# board.net
KiCad netlist of a schematic drawn in EAGLE
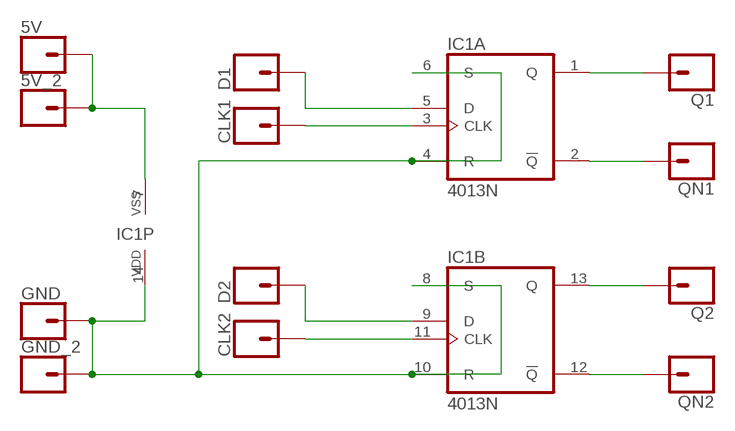
[diagram p0: schematic, sheet 1]

(export (version "E")
  (design (tool "Eeschema 10.0.6"))
  (components
    (comp (ref "5V")
      (value "CONN_01")
      (footprint "eagle-import:1X01")
      (libsource (lib "eagle-import") (part "CONN_01"))
    )
    (comp (ref "5V_2")
      (value "CONN_01")
      (footprint "eagle-import:1X01")
      (libsource (lib "eagle-import") (part "CONN_01"))
    )
    (comp (ref "CLK1")
      (value "CONN_01")
      (footprint "eagle-import:1X01")
      (libsource (lib "eagle-import") (part "CONN_01"))
    )
    (comp (ref "CLK2")
      (value "CONN_01")
      (footprint "eagle-import:1X01")
      (libsource (lib "eagle-import") (part "CONN_01"))
    )
    (comp (ref "D1")
      (value "CONN_01")
      (footprint "eagle-import:1X01")
      (libsource (lib "eagle-import") (part "CONN_01"))
    )
    (comp (ref "D2")
      (value "CONN_01")
      (footprint "eagle-import:1X01")
      (libsource (lib "eagle-import") (part "CONN_01"))
    )
    (comp (ref "GND")
      (value "CONN_01")
      (footprint "eagle-import:1X01")
      (libsource (lib "eagle-import") (part "CONN_01"))
    )
    (comp (ref "GND_2")
      (value "CONN_01")
      (footprint "eagle-import:1X01")
      (libsource (lib "eagle-import") (part "CONN_01"))
    )
    (comp (ref "IC1")
      (value "4013N")
      (footprint "eagle-import:DIL14")
      (libsource (lib "eagle-import") (part "4013N"))
    )
    (comp (ref "Q1")
      (value "CONN_01")
      (footprint "eagle-import:1X01")
      (libsource (lib "eagle-import") (part "CONN_01"))
    )
    (comp (ref "Q2")
      (value "CONN_01")
      (footprint "eagle-import:1X01")
      (libsource (lib "eagle-import") (part "CONN_01"))
    )
    (comp (ref "QN1")
      (value "CONN_01")
      (footprint "eagle-import:1X01")
      (libsource (lib "eagle-import") (part "CONN_01"))
    )
    (comp (ref "QN2")
      (value "CONN_01")
      (footprint "eagle-import:1X01")
      (libsource (lib "eagle-import") (part "CONN_01"))
    )
  )
  (nets
    (net (code "1") (name "Net-(IC1A-CLK)") (class "Default")
      (node (ref "CLK1") (pin "1") (pinfunction "1_1") (pintype "passive"))
      (node (ref "IC1") (pin "3") (pinfunction "CLK_3") (pintype "input"))
    )
    (net (code "2") (name "Net-(IC1A-D)") (class "Default")
      (node (ref "D1") (pin "1") (pinfunction "1_1") (pintype "passive"))
      (node (ref "IC1") (pin "5") (pinfunction "D_5") (pintype "input"))
    )
    (net (code "3") (name "Net-(IC1A-Q)") (class "Default")
      (node (ref "IC1") (pin "1") (pinfunction "Q_1") (pintype "output"))
      (node (ref "Q1") (pin "1") (pinfunction "1_1") (pintype "passive"))
    )
    (net (code "4") (name "Net-(IC1A-R)") (class "Default")
      (node (ref "GND") (pin "1") (pinfunction "1_1") (pintype "passive"))
      (node (ref "GND_2") (pin "1") (pinfunction "1_1") (pintype "passive"))
      (node (ref "IC1") (pin "10") (pinfunction "R_10") (pintype "input"))
      (node (ref "IC1") (pin "14") (pinfunction "VDD_14") (pintype "power_in"))
      (node (ref "IC1") (pin "4") (pinfunction "R_4") (pintype "input"))
      (node (ref "IC1") (pin "6") (pinfunction "S_6") (pintype "input"))
      (node (ref "IC1") (pin "8") (pinfunction "S_8") (pintype "input"))
    )
    (net (code "5") (name "Net-(IC1A-~{Q})") (class "Default")
      (node (ref "IC1") (pin "2") (pinfunction "~{Q}_2") (pintype "output"))
      (node (ref "QN1") (pin "1") (pinfunction "1_1") (pintype "passive"))
    )
    (net (code "6") (name "Net-(IC1B-CLK)") (class "Default")
      (node (ref "CLK2") (pin "1") (pinfunction "1_1") (pintype "passive"))
      (node (ref "IC1") (pin "11") (pinfunction "CLK_11") (pintype "input"))
    )
    (net (code "7") (name "Net-(IC1B-D)") (class "Default")
      (node (ref "D2") (pin "1") (pinfunction "1_1") (pintype "passive"))
      (node (ref "IC1") (pin "9") (pinfunction "D_9") (pintype "input"))
    )
    (net (code "8") (name "Net-(IC1B-Q)") (class "Default")
      (node (ref "IC1") (pin "13") (pinfunction "Q_13") (pintype "output"))
      (node (ref "Q2") (pin "1") (pinfunction "1_1") (pintype "passive"))
    )
    (net (code "9") (name "Net-(IC1B-~{Q})") (class "Default")
      (node (ref "IC1") (pin "12") (pinfunction "~{Q}_12") (pintype "output"))
      (node (ref "QN2") (pin "1") (pinfunction "1_1") (pintype "passive"))
    )
    (net (code "10") (name "Net-(IC1C-VSS)") (class "Default")
      (node (ref "5V") (pin "1") (pinfunction "1_1") (pintype "passive"))
      (node (ref "5V_2") (pin "1") (pinfunction "1_1") (pintype "passive"))
      (node (ref "IC1") (pin "7") (pinfunction "VSS_7") (pintype "power_in"))
    )
  )
)
